# MC21R01_EtherCAT.net
KiCad netlist of a schematic drawn in Altium Designer
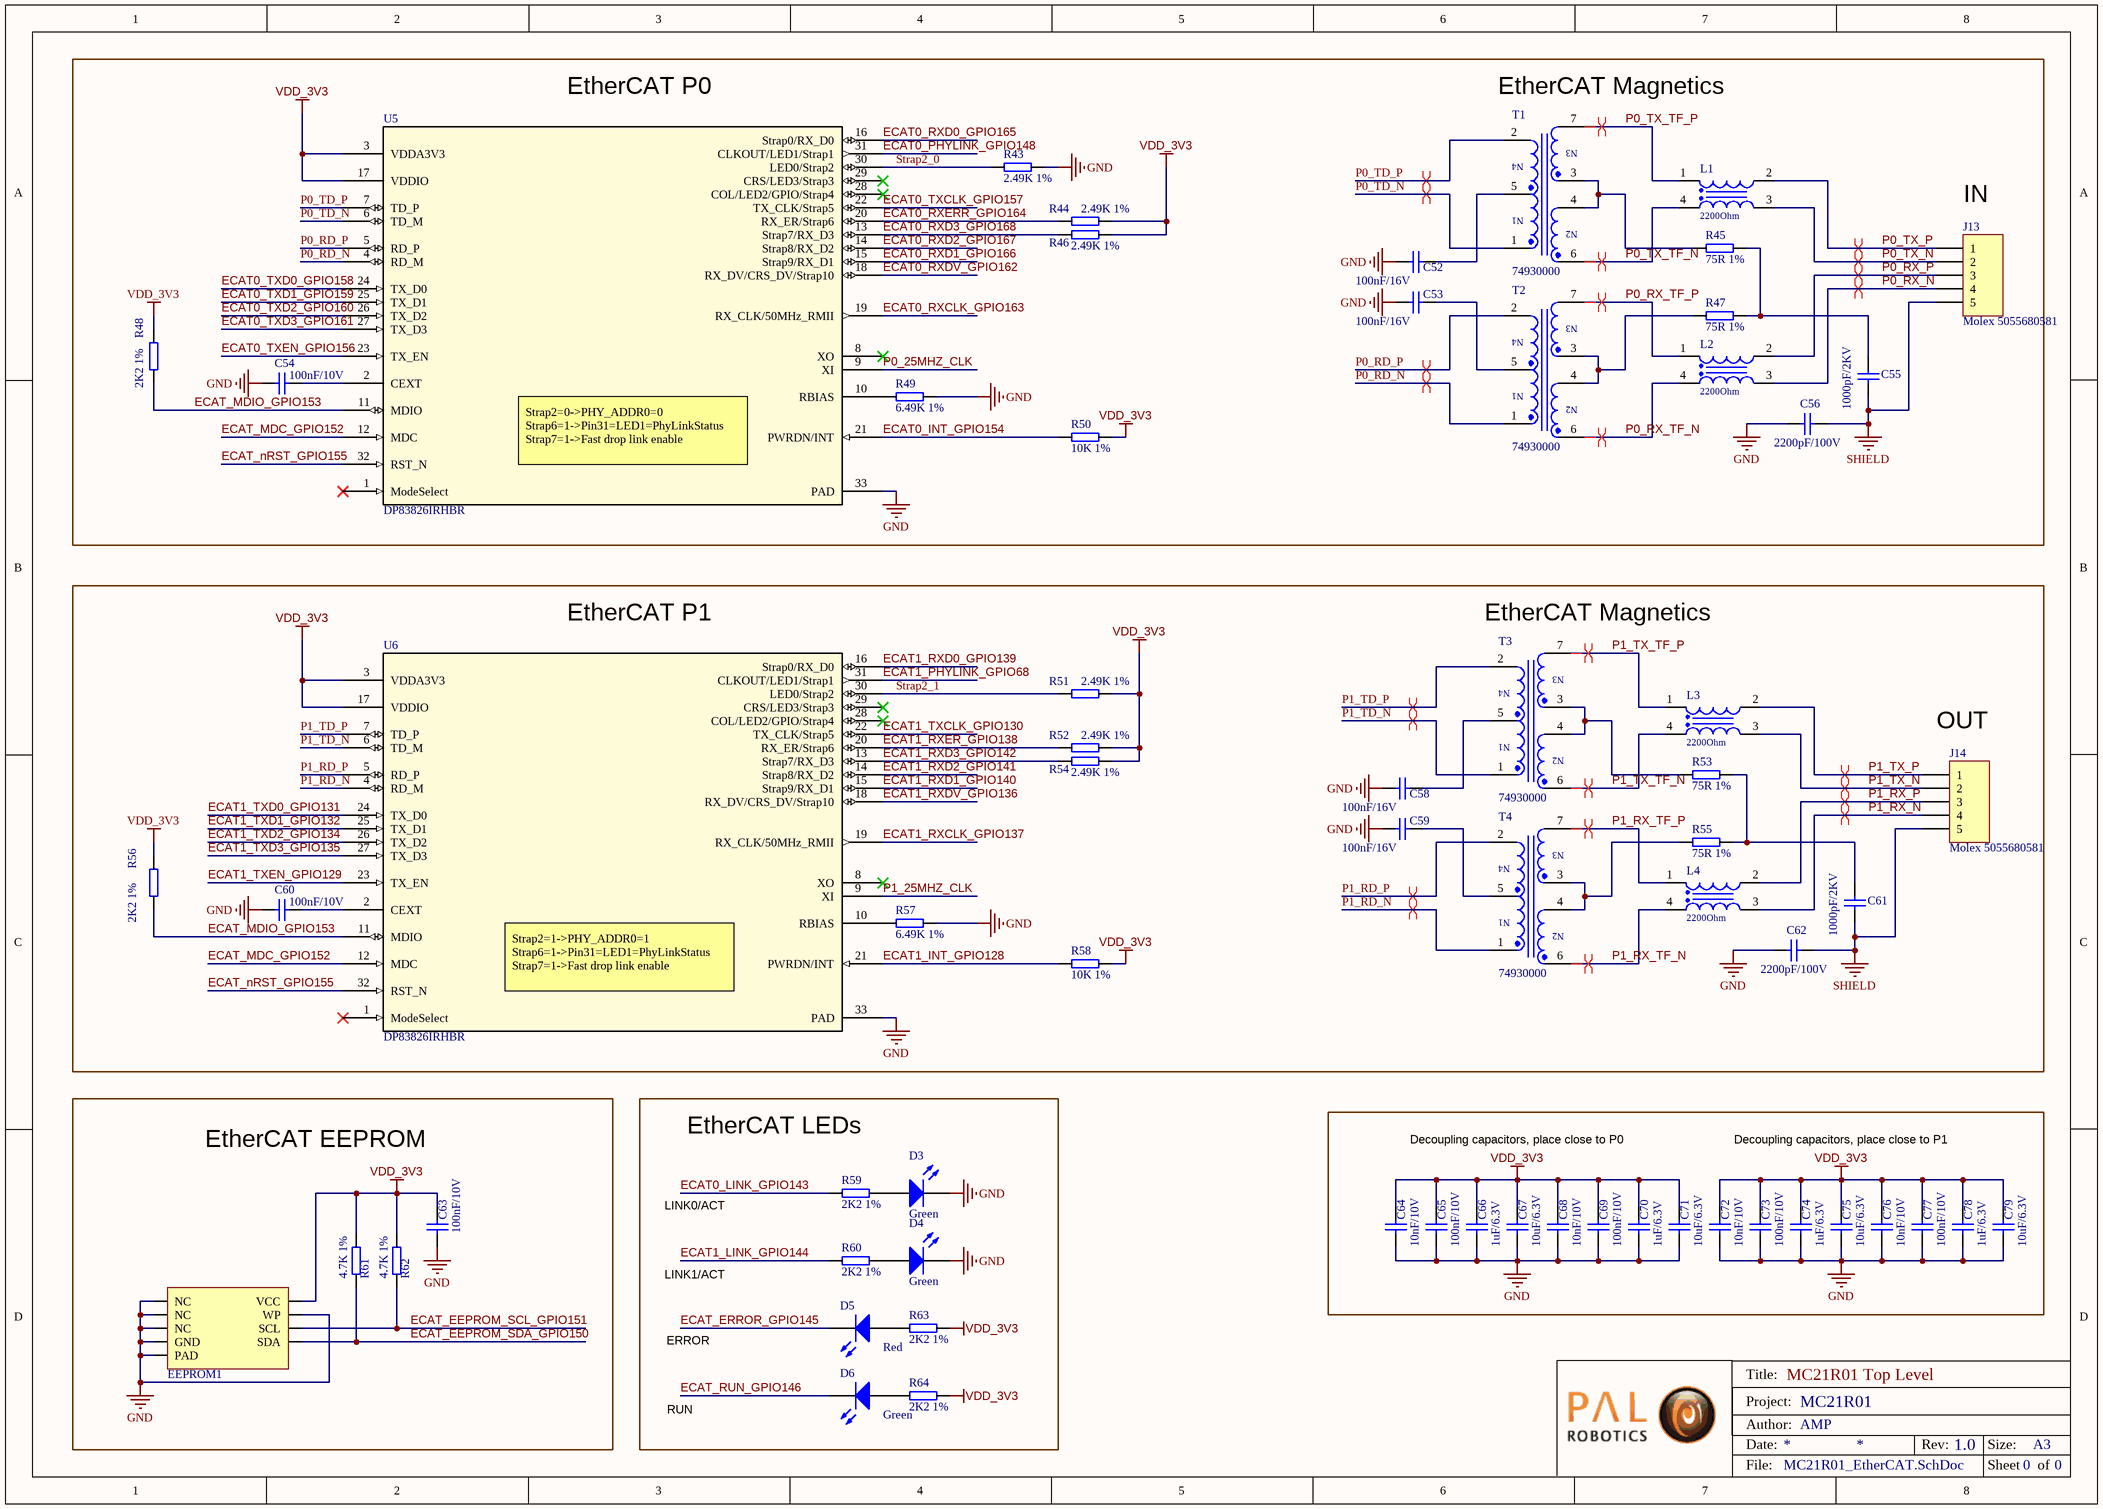
[diagram p0: MC21R01_EtherCAT.SchDoc]

(export (version "E")
  (design (tool "Eeschema 10.0.6"))
  (components
    (comp (ref "C52")
      (value "100nF/16V")
      (footprint "PAL_Capacitors:0402 SMD Capacitor")
      (description "100nF/16V 0402 10% Tolerance X7R Multilayer Ceramic Chip Capacitor")
      (fields (field (name "Comment") "100nF/16V 0402 10% X7R"))
      (libsource (lib "PAL_Capacitors") (part "100nF/16V 0402 10% X7R"))
    )
    (comp (ref "C53")
      (value "100nF/16V")
      (footprint "PAL_Capacitors:0402 SMD Capacitor")
      (description "100nF/16V 0402 10% Tolerance X7R Multilayer Ceramic Chip Capacitor")
      (fields (field (name "Comment") "100nF/16V 0402 10% X7R"))
      (libsource (lib "PAL_Capacitors") (part "100nF/16V 0402 10% X7R"))
    )
    (comp (ref "C54")
      (value "100nF/10V")
      (footprint "PAL_Capacitors:0402 SMD Capacitor")
      (description "100nF/10V 0402 20% Tolerance X5R Multilayer Ceramic Chip Capacitor")
      (fields (field (name "Comment") "100nF/10V 0402 20% X5R"))
      (libsource (lib "PAL_Capacitors") (part "100nF/10V 0402 20% X5R"))
    )
    (comp (ref "C55")
      (value "1000pF/2KV")
      (footprint "PAL_Capacitors:1206 SMD Capacitor")
      (description "1000 pF 2 KV 1206  ±10% Tolerance X7R Multilayer Ceramic Chip Capacitor")
      (libsource (lib "PAL_Capacitors") (part "1000pF/2KV 1206 10% X7R"))
    )
    (comp (ref "C56")
      (value "2200pF/100V")
      (footprint "PAL_Capacitors:0402 SMD Capacitor")
      (description "2200pF/100V 0402 10% Tolerance X7S Multilayer Ceramic Chip Capacitor")
      (fields (field (name "Comment") "2200pF/100V 0402 10% X7S"))
      (libsource (lib "PAL_Capacitors") (part "2200pF/100V 0402 10% X7S"))
    )
    (comp (ref "C58")
      (value "100nF/16V")
      (footprint "PAL_Capacitors:0402 SMD Capacitor")
      (description "100nF/16V 0402 10% Tolerance X7R Multilayer Ceramic Chip Capacitor")
      (fields (field (name "Comment") "100nF/16V 0402 10% X7R"))
      (libsource (lib "PAL_Capacitors") (part "100nF/16V 0402 10% X7R"))
    )
    (comp (ref "C59")
      (value "100nF/16V")
      (footprint "PAL_Capacitors:0402 SMD Capacitor")
      (description "100nF/16V 0402 10% Tolerance X7R Multilayer Ceramic Chip Capacitor")
      (fields (field (name "Comment") "100nF/16V 0402 10% X7R"))
      (libsource (lib "PAL_Capacitors") (part "100nF/16V 0402 10% X7R"))
    )
    (comp (ref "C60")
      (value "100nF/10V")
      (footprint "PAL_Capacitors:0402 SMD Capacitor")
      (description "100nF/10V 0402 20% Tolerance X5R Multilayer Ceramic Chip Capacitor")
      (fields (field (name "Comment") "100nF/10V 0402 20% X5R"))
      (libsource (lib "PAL_Capacitors") (part "100nF/10V 0402 20% X5R"))
    )
    (comp (ref "C61")
      (value "1000pF/2KV")
      (footprint "PAL_Capacitors:1206 SMD Capacitor")
      (description "1000 pF 2 KV 1206  ±10% Tolerance X7R Multilayer Ceramic Chip Capacitor")
      (libsource (lib "PAL_Capacitors") (part "1000pF/2KV 1206 10% X7R"))
    )
    (comp (ref "C62")
      (value "2200pF/100V")
      (footprint "PAL_Capacitors:0402 SMD Capacitor")
      (description "2200pF/100V 0402 10% Tolerance X7S Multilayer Ceramic Chip Capacitor")
      (fields (field (name "Comment") "2200pF/100V 0402 10% X7S"))
      (libsource (lib "PAL_Capacitors") (part "2200pF/100V 0402 10% X7S"))
    )
    (comp (ref "C63")
      (value "100nF/10V")
      (footprint "PAL_Capacitors:0402 SMD Capacitor")
      (description "100nF/10V 0402 20% Tolerance X5R Multilayer Ceramic Chip Capacitor")
      (fields (field (name "Comment") "100nF/10V 0402 20% X5R"))
      (libsource (lib "PAL_Capacitors") (part "100nF/10V 0402 20% X5R"))
    )
    (comp (ref "C64")
      (value "10nF/10V")
      (footprint "PAL_Capacitors:0402 SMD Capacitor")
      (description "10nF/10V 0402 20% Tolerance X5R Multilayer Ceramic Chip Capacitor")
      (fields (field (name "Comment") "10nF/10V 0402 20% X5R"))
      (libsource (lib "PAL_Capacitors") (part "10nF/10V 0402 20% X5R"))
    )
    (comp (ref "C65")
      (value "100nF/10V")
      (footprint "PAL_Capacitors:0402 SMD Capacitor")
      (description "100nF/10V 0402 20% Tolerance X5R Multilayer Ceramic Chip Capacitor")
      (fields (field (name "Comment") "100nF/10V 0402 20% X5R"))
      (libsource (lib "PAL_Capacitors") (part "100nF/10V 0402 20% X5R"))
    )
    (comp (ref "C66")
      (value "1uF/6.3V")
      (footprint "PAL_Capacitors:0402 SMD Capacitor")
      (description "1uF/6.3V 0402 10% Tolerance X5R Multilayer Ceramic Chip Capacitor")
      (fields (field (name "Comment") "1uF/6.3V 0402 10% X5R"))
      (libsource (lib "PAL_Capacitors") (part "1uF/6.3V 0402 10% X5R"))
    )
    (comp (ref "C67")
      (value "10uF/6.3V")
      (footprint "PAL_Capacitors:0402 SMD Capacitor")
      (description "10uF/6.3V 0402 20% Tolerance X5R Multilayer Ceramic Chip Capacitor")
      (fields (field (name "Comment") "10uF/6.3V 0402 20% X5R"))
      (libsource (lib "PAL_Capacitors") (part "10uF/6.3V 0402 20% X5R"))
    )
    (comp (ref "C68")
      (value "10nF/10V")
      (footprint "PAL_Capacitors:0402 SMD Capacitor")
      (description "10nF/10V 0402 20% Tolerance X5R Multilayer Ceramic Chip Capacitor")
      (fields (field (name "Comment") "10nF/10V 0402 20% X5R"))
      (libsource (lib "PAL_Capacitors") (part "10nF/10V 0402 20% X5R"))
    )
    (comp (ref "C69")
      (value "100nF/10V")
      (footprint "PAL_Capacitors:0402 SMD Capacitor")
      (description "100nF/10V 0402 20% Tolerance X5R Multilayer Ceramic Chip Capacitor")
      (fields (field (name "Comment") "100nF/10V 0402 20% X5R"))
      (libsource (lib "PAL_Capacitors") (part "100nF/10V 0402 20% X5R"))
    )
    (comp (ref "C70")
      (value "1uF/6.3V")
      (footprint "PAL_Capacitors:0402 SMD Capacitor")
      (description "1uF/6.3V 0402 10% Tolerance X5R Multilayer Ceramic Chip Capacitor")
      (fields (field (name "Comment") "1uF/6.3V 0402 10% X5R"))
      (libsource (lib "PAL_Capacitors") (part "1uF/6.3V 0402 10% X5R"))
    )
    (comp (ref "C71")
      (value "10uF/6.3V")
      (footprint "PAL_Capacitors:0402 SMD Capacitor")
      (description "10uF/6.3V 0402 20% Tolerance X5R Multilayer Ceramic Chip Capacitor")
      (fields (field (name "Comment") "10uF/6.3V 0402 20% X5R"))
      (libsource (lib "PAL_Capacitors") (part "10uF/6.3V 0402 20% X5R"))
    )
    (comp (ref "C72")
      (value "10nF/10V")
      (footprint "PAL_Capacitors:0402 SMD Capacitor")
      (description "10nF/10V 0402 20% Tolerance X5R Multilayer Ceramic Chip Capacitor")
      (fields (field (name "Comment") "10nF/10V 0402 20% X5R"))
      (libsource (lib "PAL_Capacitors") (part "10nF/10V 0402 20% X5R"))
    )
    (comp (ref "C73")
      (value "100nF/10V")
      (footprint "PAL_Capacitors:0402 SMD Capacitor")
      (description "100nF/10V 0402 20% Tolerance X5R Multilayer Ceramic Chip Capacitor")
      (fields (field (name "Comment") "100nF/10V 0402 20% X5R"))
      (libsource (lib "PAL_Capacitors") (part "100nF/10V 0402 20% X5R"))
    )
    (comp (ref "C74")
      (value "1uF/6.3V")
      (footprint "PAL_Capacitors:0402 SMD Capacitor")
      (description "1uF/6.3V 0402 10% Tolerance X5R Multilayer Ceramic Chip Capacitor")
      (fields (field (name "Comment") "1uF/6.3V 0402 10% X5R"))
      (libsource (lib "PAL_Capacitors") (part "1uF/6.3V 0402 10% X5R"))
    )
    (comp (ref "C75")
      (value "10uF/6.3V")
      (footprint "PAL_Capacitors:0402 SMD Capacitor")
      (description "10uF/6.3V 0402 20% Tolerance X5R Multilayer Ceramic Chip Capacitor")
      (fields (field (name "Comment") "10uF/6.3V 0402 20% X5R"))
      (libsource (lib "PAL_Capacitors") (part "10uF/6.3V 0402 20% X5R"))
    )
    (comp (ref "C76")
      (value "10nF/10V")
      (footprint "PAL_Capacitors:0402 SMD Capacitor")
      (description "10nF/10V 0402 20% Tolerance X5R Multilayer Ceramic Chip Capacitor")
      (fields (field (name "Comment") "10nF/10V 0402 20% X5R"))
      (libsource (lib "PAL_Capacitors") (part "10nF/10V 0402 20% X5R"))
    )
    (comp (ref "C77")
      (value "100nF/10V")
      (footprint "PAL_Capacitors:0402 SMD Capacitor")
      (description "100nF/10V 0402 20% Tolerance X5R Multilayer Ceramic Chip Capacitor")
      (fields (field (name "Comment") "100nF/10V 0402 20% X5R"))
      (libsource (lib "PAL_Capacitors") (part "100nF/10V 0402 20% X5R"))
    )
    (comp (ref "C78")
      (value "1uF/6.3V")
      (footprint "PAL_Capacitors:0402 SMD Capacitor")
      (description "1uF/6.3V 0402 10% Tolerance X5R Multilayer Ceramic Chip Capacitor")
      (fields (field (name "Comment") "1uF/6.3V 0402 10% X5R"))
      (libsource (lib "PAL_Capacitors") (part "1uF/6.3V 0402 10% X5R"))
    )
    (comp (ref "C79")
      (value "10uF/6.3V")
      (footprint "PAL_Capacitors:0402 SMD Capacitor")
      (description "10uF/6.3V 0402 20% Tolerance X5R Multilayer Ceramic Chip Capacitor")
      (fields (field (name "Comment") "10uF/6.3V 0402 20% X5R"))
      (libsource (lib "PAL_Capacitors") (part "10uF/6.3V 0402 20% X5R"))
    )
    (comp (ref "D3")
      (value "Green")
      (footprint "0402 SMD LED GREEN")
      (description "Low Profile Chip LED, Green")
      (fields (field (name "MANUFACTURER") "ROHM") (field (name "MANUFACTURER PART NUMBER") "SML-P11MTT86R"))
      (libsource (lib "PAL_devices") (part "LED_0402_green"))
    )
    (comp (ref "D4")
      (value "Green")
      (footprint "0402 SMD LED GREEN")
      (description "Low Profile Chip LED, Green")
      (fields (field (name "MANUFACTURER") "ROHM") (field (name "MANUFACTURER PART NUMBER") "SML-P11MTT86R"))
      (libsource (lib "PAL_devices") (part "LED_0402_green"))
    )
    (comp (ref "D5")
      (value "Red")
      (footprint "0402 SMD LED Red")
      (description "Low Profile Chip LED, Red")
      (fields (field (name "MANUFACTURER") "ROHM") (field (name "MANUFACTURER PART NUMBER") "SML-P11UTT86R"))
      (libsource (lib "PAL_devices") (part "LED_0402_Red"))
    )
    (comp (ref "D6")
      (value "Green")
      (footprint "0402 SMD LED GREEN")
      (description "Low Profile Chip LED, Green")
      (fields (field (name "MANUFACTURER") "ROHM") (field (name "MANUFACTURER PART NUMBER") "SML-P11MTT86R"))
      (libsource (lib "PAL_devices") (part "LED_0402_green"))
    )
    (comp (ref "EEPROM1")
      (value "CAT24C16HU4I-GT3")
      (footprint "PAL_IPC-7351_2020 :PQFN50P300X200X50_HS-9N")
      (description "CAT24C16 Series 16 Kb (2K x 8) 400 kHz I2C CMOS Serial EEPROM - UDFN-8EP")
      (fields (field (name "MANUFACTURER") "ON Semi") (field (name "CREATED BY") "AMP"))
      (libsource (lib "PAL_Memory_2020") (part "CAT24C16HU4I-GT3"))
    )
    (comp (ref "J13")
      (value "Molex 5055680581")
      (footprint "PAL_Molex_Micro-Lock_2020:Molex 5055680581")
      (fields
        (field (name "MANUFACTURER") "Molex")
        (field (name "MANUFACTURER PART NUMBER") "5055680581")
        (field (name "MATING PART NUMBER") "Molex 5055650501")
        (field (name "CREATED BY") "AMP")
      )
      (libsource (lib "PAL_Molex_Micro-Lock_2020") (part "Molex 5055680581"))
    )
    (comp (ref "J14")
      (value "Molex 5055680581")
      (footprint "PAL_Molex_Micro-Lock_2020:Molex 5055680581")
      (fields
        (field (name "MANUFACTURER") "Molex")
        (field (name "MANUFACTURER PART NUMBER") "5055680581")
        (field (name "MATING PART NUMBER") "Molex 5055650501")
        (field (name "CREATED BY") "AMP")
      )
      (libsource (lib "PAL_Molex_Micro-Lock_2020") (part "Molex 5055680581"))
    )
    (comp (ref "L1")
      (value "2200Ohm")
      (footprint "PAL_Wurth:744232222")
      (description "WE-CNSW SMT Common Mode Line Filter, size 1206, 2200Ohm, 0.2A, 50V")
      (fields
        (field (name "MANUFACTURER PART NUMBER") "744232222")
        (field (name "MANUFACTURER") "Wurth Elektronik")
      )
      (libsource (lib "PAL_Wurth") (part "744232222"))
    )
    (comp (ref "L2")
      (value "2200Ohm")
      (footprint "PAL_Wurth:744232222")
      (description "WE-CNSW SMT Common Mode Line Filter, size 1206, 2200Ohm, 0.2A, 50V")
      (fields
        (field (name "MANUFACTURER PART NUMBER") "744232222")
        (field (name "MANUFACTURER") "Wurth Elektronik")
      )
      (libsource (lib "PAL_Wurth") (part "744232222"))
    )
    (comp (ref "L3")
      (value "2200Ohm")
      (footprint "PAL_Wurth:744232222")
      (description "WE-CNSW SMT Common Mode Line Filter, size 1206, 2200Ohm, 0.2A, 50V")
      (fields
        (field (name "MANUFACTURER PART NUMBER") "744232222")
        (field (name "MANUFACTURER") "Wurth Elektronik")
      )
      (libsource (lib "PAL_Wurth") (part "744232222"))
    )
    (comp (ref "L4")
      (value "2200Ohm")
      (footprint "PAL_Wurth:744232222")
      (description "WE-CNSW SMT Common Mode Line Filter, size 1206, 2200Ohm, 0.2A, 50V")
      (fields
        (field (name "MANUFACTURER PART NUMBER") "744232222")
        (field (name "MANUFACTURER") "Wurth Elektronik")
      )
      (libsource (lib "PAL_Wurth") (part "744232222"))
    )
    (comp (ref "R43")
      (value "2.49K 1%")
      (footprint "0402 SMD rESISTOR")
      (description "2.49K/50V 1% 0402 100mW SMD Resistor")
      (libsource (lib "PAL_Resistors") (part "2.49K/50V 1% 0402 100mW"))
    )
    (comp (ref "R44")
      (value "2.49K 1%")
      (footprint "0402 SMD rESISTOR")
      (description "2.49K/50V 1% 0402 100mW SMD Resistor")
      (libsource (lib "PAL_Resistors") (part "2.49K/50V 1% 0402 100mW"))
    )
    (comp (ref "R45")
      (value "75R 1%")
      (footprint "0402 SMD rESISTOR")
      (description "75R/50V 1% 0402 100mW SMD Resistor")
      (libsource (lib "PAL_Resistors") (part "75R/50V 1% 0402 100mW"))
    )
    (comp (ref "R46")
      (value "2.49K 1%")
      (footprint "0402 SMD rESISTOR")
      (description "2.49K/50V 1% 0402 100mW SMD Resistor")
      (libsource (lib "PAL_Resistors") (part "2.49K/50V 1% 0402 100mW"))
    )
    (comp (ref "R47")
      (value "75R 1%")
      (footprint "0402 SMD rESISTOR")
      (description "75R/50V 1% 0402 100mW SMD Resistor")
      (libsource (lib "PAL_Resistors") (part "75R/50V 1% 0402 100mW"))
    )
    (comp (ref "R48")
      (value "2K2 1%")
      (footprint "0402 SMD rESISTOR")
      (description "2K2/50V 1% 0402 100mW SMD Resistor")
      (libsource (lib "PAL_Resistors") (part "2K2/50V 1% 0402 100mW"))
    )
    (comp (ref "R49")
      (value "6.49K 1%")
      (footprint "0402 SMD rESISTOR")
      (description "6.49K/50V 1% 0402 100mW SMD Resistor")
      (libsource (lib "PAL_Resistors") (part "6.49K/50V 1% 0402 100mW"))
    )
    (comp (ref "R50")
      (value "10K 1%")
      (footprint "0402 SMD rESISTOR")
      (description "10K/50V 1% 0402 100mW SMD Resistor")
      (libsource (lib "PAL_Resistors") (part "10K/50V 1% 0402 100mW"))
    )
    (comp (ref "R51")
      (value "2.49K 1%")
      (footprint "0402 SMD rESISTOR")
      (description "2.49K/50V 1% 0402 100mW SMD Resistor")
      (libsource (lib "PAL_Resistors") (part "2.49K/50V 1% 0402 100mW"))
    )
    (comp (ref "R52")
      (value "2.49K 1%")
      (footprint "0402 SMD rESISTOR")
      (description "2.49K/50V 1% 0402 100mW SMD Resistor")
      (libsource (lib "PAL_Resistors") (part "2.49K/50V 1% 0402 100mW"))
    )
    (comp (ref "R53")
      (value "75R 1%")
      (footprint "0402 SMD rESISTOR")
      (description "75R/50V 1% 0402 100mW SMD Resistor")
      (libsource (lib "PAL_Resistors") (part "75R/50V 1% 0402 100mW"))
    )
    (comp (ref "R54")
      (value "2.49K 1%")
      (footprint "0402 SMD rESISTOR")
      (description "2.49K/50V 1% 0402 100mW SMD Resistor")
      (libsource (lib "PAL_Resistors") (part "2.49K/50V 1% 0402 100mW"))
    )
    (comp (ref "R55")
      (value "75R 1%")
      (footprint "0402 SMD rESISTOR")
      (description "75R/50V 1% 0402 100mW SMD Resistor")
      (libsource (lib "PAL_Resistors") (part "75R/50V 1% 0402 100mW"))
    )
    (comp (ref "R56")
      (value "2K2 1%")
      (footprint "0402 SMD rESISTOR")
      (description "2K2/50V 1% 0402 100mW SMD Resistor")
      (libsource (lib "PAL_Resistors") (part "2K2/50V 1% 0402 100mW"))
    )
    (comp (ref "R57")
      (value "6.49K 1%")
      (footprint "0402 SMD rESISTOR")
      (description "6.49K/50V 1% 0402 100mW SMD Resistor")
      (libsource (lib "PAL_Resistors") (part "6.49K/50V 1% 0402 100mW"))
    )
    (comp (ref "R58")
      (value "10K 1%")
      (footprint "0402 SMD rESISTOR")
      (description "10K/50V 1% 0402 100mW SMD Resistor")
      (libsource (lib "PAL_Resistors") (part "10K/50V 1% 0402 100mW"))
    )
    (comp (ref "R59")
      (value "2K2 1%")
      (footprint "0402 SMD rESISTOR")
      (description "2K2/50V 1% 0402 100mW SMD Resistor")
      (libsource (lib "PAL_Resistors") (part "2K2/50V 1% 0402 100mW"))
    )
    (comp (ref "R60")
      (value "2K2 1%")
      (footprint "0402 SMD rESISTOR")
      (description "2K2/50V 1% 0402 100mW SMD Resistor")
      (libsource (lib "PAL_Resistors") (part "2K2/50V 1% 0402 100mW"))
    )
    (comp (ref "R61")
      (value "4.7K 1%")
      (footprint "0402 SMD rESISTOR")
      (description "4.7K/50V 1% 0402 100mW SMD Resistor")
      (libsource (lib "PAL_Resistors") (part "4.7K/50V 1% 0402 100mW"))
    )
    (comp (ref "R62")
      (value "4.7K 1%")
      (footprint "0402 SMD rESISTOR")
      (description "4.7K/50V 1% 0402 100mW SMD Resistor")
      (libsource (lib "PAL_Resistors") (part "4.7K/50V 1% 0402 100mW"))
    )
    (comp (ref "R63")
      (value "2K2 1%")
      (footprint "0402 SMD rESISTOR")
      (description "2K2/50V 1% 0402 100mW SMD Resistor")
      (libsource (lib "PAL_Resistors") (part "2K2/50V 1% 0402 100mW"))
    )
    (comp (ref "R64")
      (value "2K2 1%")
      (footprint "0402 SMD rESISTOR")
      (description "2K2/50V 1% 0402 100mW SMD Resistor")
      (libsource (lib "PAL_Resistors") (part "2K2/50V 1% 0402 100mW"))
    )
    (comp (ref "T1")
      (value "74930000")
      (footprint "PAL_Wurth:74930000")
      (description "WE-STST Super Tiny Signal Transformer, size 4532, 350uH")
      (fields (field (name "PUBLISHER") "Wurth Elektronik"))
      (libsource (lib "PAL_Wurth") (part "74930000"))
    )
    (comp (ref "T2")
      (value "74930000")
      (footprint "PAL_Wurth:74930000")
      (description "WE-STST Super Tiny Signal Transformer, size 4532, 350uH")
      (fields (field (name "PUBLISHER") "Wurth Elektronik"))
      (libsource (lib "PAL_Wurth") (part "74930000"))
    )
    (comp (ref "T3")
      (value "74930000")
      (footprint "PAL_Wurth:74930000")
      (description "WE-STST Super Tiny Signal Transformer, size 4532, 350uH")
      (fields (field (name "PUBLISHER") "Wurth Elektronik"))
      (libsource (lib "PAL_Wurth") (part "74930000"))
    )
    (comp (ref "T4")
      (value "74930000")
      (footprint "PAL_Wurth:74930000")
      (description "WE-STST Super Tiny Signal Transformer, size 4532, 350uH")
      (fields (field (name "PUBLISHER") "Wurth Elektronik"))
      (libsource (lib "PAL_Wurth") (part "74930000"))
    )
    (comp (ref "U5")
      (value "DP83826IRHBR")
      (footprint "RHB0032B")
      (fields (field (name "MANUFACTURER") "Texas Instruments"))
      (libsource (lib "TI-DP8382x") (part "DP83826IRHBR"))
    )
    (comp (ref "U6")
      (value "DP83826IRHBR")
      (footprint "RHB0032B")
      (fields (field (name "MANUFACTURER") "Texas Instruments"))
      (libsource (lib "TI-DP8382x") (part "DP83826IRHBR"))
    )
  )
  (nets
    (net (code "1") (name "/ECAT0_INT_GPIO154") (class "Default")
      (node (ref "R50") (pin "2") (pinfunction "2_2") (pintype "passive"))
      (node (ref "U5") (pin "21") (pinfunction "PWRDN/INT_21") (pintype "input"))
    )
    (net (code "2") (name "/ECAT0_LINK_GPIO143") (class "Default")
      (node (ref "R59") (pin "2") (pinfunction "2_2") (pintype "passive"))
    )
    (net (code "3") (name "/ECAT0_PHYLINK_GPIO148") (class "Default")
      (node (ref "U5") (pin "31") (pinfunction "CLKOUT/LED1/Strap1_31") (pintype "output"))
    )
    (net (code "4") (name "/ECAT0_RXCLK_GPIO163") (class "Default")
      (node (ref "U5") (pin "19") (pinfunction "RX_CLK/50MHz_RMII_19") (pintype "output"))
    )
    (net (code "5") (name "/ECAT0_RXD0_GPIO165") (class "Default")
      (node (ref "U5") (pin "16") (pinfunction "Strap0/RX_D0_16") (pintype "bidirectional"))
    )
    (net (code "6") (name "/ECAT0_RXD1_GPIO166") (class "Default")
      (node (ref "U5") (pin "15") (pinfunction "Strap9/RX_D1_15") (pintype "bidirectional"))
    )
    (net (code "7") (name "/ECAT0_RXD2_GPIO167") (class "Default")
      (node (ref "U5") (pin "14") (pinfunction "Strap8/RX_D2_14") (pintype "bidirectional"))
    )
    (net (code "8") (name "/ECAT0_RXD3_GPIO168") (class "Default")
      (node (ref "R46") (pin "1") (pinfunction "1_1") (pintype "passive"))
      (node (ref "U5") (pin "13") (pinfunction "Strap7/RX_D3_13") (pintype "bidirectional"))
    )
    (net (code "9") (name "/ECAT0_RXDV_GPIO162") (class "Default")
      (node (ref "U5") (pin "18") (pinfunction "RX_DV/CRS_DV/Strap10_18") (pintype "bidirectional"))
    )
    (net (code "10") (name "/ECAT0_RXERR_GPIO164") (class "Default")
      (node (ref "R44") (pin "2") (pinfunction "2_2") (pintype "passive"))
      (node (ref "U5") (pin "20") (pinfunction "RX_ER/Strap6_20") (pintype "bidirectional"))
    )
    (net (code "11") (name "/ECAT0_TXCLK_GPIO157") (class "Default")
      (node (ref "U5") (pin "22") (pinfunction "TX_CLK/Strap5_22") (pintype "bidirectional"))
    )
    (net (code "12") (name "/ECAT0_TXD0_GPIO158") (class "Default")
      (node (ref "U5") (pin "24") (pinfunction "TX_D0_24") (pintype "input"))
    )
    (net (code "13") (name "/ECAT0_TXD1_GPIO159") (class "Default")
      (node (ref "U5") (pin "25") (pinfunction "TX_D1_25") (pintype "input"))
    )
    (net (code "14") (name "/ECAT0_TXD2_GPIO160") (class "Default")
      (node (ref "U5") (pin "26") (pinfunction "TX_D2_26") (pintype "input"))
    )
    (net (code "15") (name "/ECAT0_TXD3_GPIO161") (class "Default")
      (node (ref "U5") (pin "27") (pinfunction "TX_D3_27") (pintype "input"))
    )
    (net (code "16") (name "/ECAT0_TXEN_GPIO156") (class "Default")
      (node (ref "U5") (pin "23") (pinfunction "TX_EN_23") (pintype "input"))
    )
    (net (code "17") (name "/ECAT1_INT_GPIO128") (class "Default")
      (node (ref "R58") (pin "2") (pinfunction "2_2") (pintype "passive"))
      (node (ref "U6") (pin "21") (pinfunction "PWRDN/INT_21") (pintype "input"))
    )
    (net (code "18") (name "/ECAT1_LINK_GPIO144") (class "Default")
      (node (ref "R60") (pin "2") (pinfunction "2_2") (pintype "passive"))
    )
    (net (code "19") (name "/ECAT1_PHYLINK_GPIO68") (class "Default")
      (node (ref "U6") (pin "31") (pinfunction "CLKOUT/LED1/Strap1_31") (pintype "output"))
    )
    (net (code "20") (name "/ECAT1_RXCLK_GPIO137") (class "Default")
      (node (ref "U6") (pin "19") (pinfunction "RX_CLK/50MHz_RMII_19") (pintype "output"))
    )
    (net (code "21") (name "/ECAT1_RXD0_GPIO139") (class "Default")
      (node (ref "U6") (pin "16") (pinfunction "Strap0/RX_D0_16") (pintype "bidirectional"))
    )
    (net (code "22") (name "/ECAT1_RXD1_GPIO140") (class "Default")
      (node (ref "U6") (pin "15") (pinfunction "Strap9/RX_D1_15") (pintype "bidirectional"))
    )
    (net (code "23") (name "/ECAT1_RXD2_GPIO141") (class "Default")
      (node (ref "U6") (pin "14") (pinfunction "Strap8/RX_D2_14") (pintype "bidirectional"))
    )
    (net (code "24") (name "/ECAT1_RXD3_GPIO142") (class "Default")
      (node (ref "R54") (pin "1") (pinfunction "1_1") (pintype "passive"))
      (node (ref "U6") (pin "13") (pinfunction "Strap7/RX_D3_13") (pintype "bidirectional"))
    )
    (net (code "25") (name "/ECAT1_RXDV_GPIO136") (class "Default")
      (node (ref "U6") (pin "18") (pinfunction "RX_DV/CRS_DV/Strap10_18") (pintype "bidirectional"))
    )
    (net (code "26") (name "/ECAT1_RXER_GPIO138") (class "Default")
      (node (ref "R52") (pin "2") (pinfunction "2_2") (pintype "passive"))
      (node (ref "U6") (pin "20") (pinfunction "RX_ER/Strap6_20") (pintype "bidirectional"))
    )
    (net (code "27") (name "/ECAT1_TXCLK_GPIO130") (class "Default")
      (node (ref "U6") (pin "22") (pinfunction "TX_CLK/Strap5_22") (pintype "bidirectional"))
    )
    (net (code "28") (name "/ECAT1_TXD0_GPIO131") (class "Default")
      (node (ref "U6") (pin "24") (pinfunction "TX_D0_24") (pintype "input"))
    )
    (net (code "29") (name "/ECAT1_TXD1_GPIO132") (class "Default")
      (node (ref "U6") (pin "25") (pinfunction "TX_D1_25") (pintype "input"))
    )
    (net (code "30") (name "/ECAT1_TXD2_GPIO134") (class "Default")
      (node (ref "U6") (pin "26") (pinfunction "TX_D2_26") (pintype "input"))
    )
    (net (code "31") (name "/ECAT1_TXD3_GPIO135") (class "Default")
      (node (ref "U6") (pin "27") (pinfunction "TX_D3_27") (pintype "input"))
    )
    (net (code "32") (name "/ECAT1_TXEN_GPIO129") (class "Default")
      (node (ref "U6") (pin "23") (pinfunction "TX_EN_23") (pintype "input"))
    )
    (net (code "33") (name "/ECAT_EEPROM_SCL_GPIO151") (class "Default")
      (node (ref "EEPROM1") (pin "6") (pinfunction "SCL_6") (pintype "passive"))
      (node (ref "R62") (pin "1") (pinfunction "1_1") (pintype "passive"))
    )
    (net (code "34") (name "/ECAT_EEPROM_SDA_GPIO150") (class "Default")
      (node (ref "EEPROM1") (pin "5") (pinfunction "SDA_5") (pintype "passive"))
      (node (ref "R61") (pin "1") (pinfunction "1_1") (pintype "passive"))
    )
    (net (code "35") (name "/ECAT_ERROR_GPIO145") (class "Default")
      (node (ref "D5") (pin "K") (pinfunction "K_K") (pintype "passive"))
    )
    (net (code "36") (name "/ECAT_MDC_GPIO152") (class "Default")
      (node (ref "U5") (pin "12") (pinfunction "MDC_12") (pintype "input"))
      (node (ref "U6") (pin "12") (pinfunction "MDC_12") (pintype "input"))
    )
    (net (code "37") (name "/ECAT_MDIO_GPIO153") (class "Default")
      (node (ref "R48") (pin "1") (pinfunction "1_1") (pintype "passive"))
      (node (ref "R56") (pin "1") (pinfunction "1_1") (pintype "passive"))
      (node (ref "U5") (pin "11") (pinfunction "MDIO_11") (pintype "bidirectional"))
      (node (ref "U6") (pin "11") (pinfunction "MDIO_11") (pintype "bidirectional"))
    )
    (net (code "38") (name "/ECAT_RUN_GPIO146") (class "Default")
      (node (ref "D6") (pin "K") (pinfunction "K_K") (pintype "passive"))
    )
    (net (code "39") (name "/ECAT_nRST_GPIO155") (class "Default")
      (node (ref "U5") (pin "32") (pinfunction "RST_N_32") (pintype "input"))
      (node (ref "U6") (pin "32") (pinfunction "RST_N_32") (pintype "input"))
    )
    (net (code "40") (name "/P0_25MHZ_CLK") (class "Default")
      (node (ref "U5") (pin "9") (pinfunction "XI_9") (pintype "passive"))
    )
    (net (code "41") (name "/P0_RD_N") (class "Default")
      (node (ref "T2") (pin "1") (pinfunction "1_1") (pintype "passive"))
      (node (ref "U5") (pin "4") (pinfunction "RD_M_4") (pintype "bidirectional"))
    )
    (net (code "42") (name "/P0_RD_P") (class "Default")
      (node (ref "T2") (pin "2") (pinfunction "2_2") (pintype "passive"))
      (node (ref "U5") (pin "5") (pinfunction "RD_P_5") (pintype "bidirectional"))
    )
    (net (code "43") (name "/P0_RX_N") (class "Default")
      (node (ref "J13") (pin "4") (pinfunction "4_4") (pintype "passive"))
      (node (ref "L2") (pin "3") (pinfunction "3_3") (pintype "passive"))
    )
    (net (code "44") (name "/P0_RX_P") (class "Default")
      (node (ref "J13") (pin "3") (pinfunction "3_3") (pintype "passive"))
      (node (ref "L2") (pin "2") (pinfunction "2_2") (pintype "passive"))
    )
    (net (code "45") (name "/P0_RX_TF_N") (class "Default")
      (node (ref "L2") (pin "4") (pinfunction "4_4") (pintype "passive"))
      (node (ref "T2") (pin "6") (pinfunction "6_6") (pintype "passive"))
    )
    (net (code "46") (name "/P0_RX_TF_P") (class "Default")
      (node (ref "L2") (pin "1") (pinfunction "1_1") (pintype "passive"))
      (node (ref "T2") (pin "7") (pinfunction "7_7") (pintype "passive"))
    )
    (net (code "47") (name "/P0_TD_N") (class "Default")
      (node (ref "T1") (pin "1") (pinfunction "1_1") (pintype "passive"))
      (node (ref "U5") (pin "6") (pinfunction "TD_M_6") (pintype "bidirectional"))
    )
    (net (code "48") (name "/P0_TD_P") (class "Default")
      (node (ref "T1") (pin "2") (pinfunction "2_2") (pintype "passive"))
      (node (ref "U5") (pin "7") (pinfunction "TD_P_7") (pintype "bidirectional"))
    )
    (net (code "49") (name "/P0_TX_N") (class "Default")
      (node (ref "J13") (pin "2") (pinfunction "2_2") (pintype "passive"))
      (node (ref "L1") (pin "3") (pinfunction "3_3") (pintype "passive"))
    )
    (net (code "50") (name "/P0_TX_P") (class "Default")
      (node (ref "J13") (pin "1") (pinfunction "1_1") (pintype "passive"))
      (node (ref "L1") (pin "2") (pinfunction "2_2") (pintype "passive"))
    )
    (net (code "51") (name "/P0_TX_TF_N") (class "Default")
      (node (ref "L1") (pin "4") (pinfunction "4_4") (pintype "passive"))
      (node (ref "T1") (pin "6") (pinfunction "6_6") (pintype "passive"))
    )
    (net (code "52") (name "/P0_TX_TF_P") (class "Default")
      (node (ref "L1") (pin "1") (pinfunction "1_1") (pintype "passive"))
      (node (ref "T1") (pin "7") (pinfunction "7_7") (pintype "passive"))
    )
    (net (code "53") (name "/P1_25MHZ_CLK") (class "Default")
      (node (ref "U6") (pin "9") (pinfunction "XI_9") (pintype "passive"))
    )
    (net (code "54") (name "/P1_RD_N") (class "Default")
      (node (ref "T4") (pin "1") (pinfunction "1_1") (pintype "passive"))
      (node (ref "U6") (pin "4") (pinfunction "RD_M_4") (pintype "bidirectional"))
    )
    (net (code "55") (name "/P1_RD_P") (class "Default")
      (node (ref "T4") (pin "2") (pinfunction "2_2") (pintype "passive"))
      (node (ref "U6") (pin "5") (pinfunction "RD_P_5") (pintype "bidirectional"))
    )
    (net (code "56") (name "/P1_RX_N") (class "Default")
      (node (ref "J14") (pin "4") (pinfunction "4_4") (pintype "passive"))
      (node (ref "L4") (pin "3") (pinfunction "3_3") (pintype "passive"))
    )
    (net (code "57") (name "/P1_RX_P") (class "Default")
      (node (ref "J14") (pin "3") (pinfunction "3_3") (pintype "passive"))
      (node (ref "L4") (pin "2") (pinfunction "2_2") (pintype "passive"))
    )
    (net (code "58") (name "/P1_RX_TF_N") (class "Default")
      (node (ref "L4") (pin "4") (pinfunction "4_4") (pintype "passive"))
      (node (ref "T4") (pin "6") (pinfunction "6_6") (pintype "passive"))
    )
    (net (code "59") (name "/P1_RX_TF_P") (class "Default")
      (node (ref "L4") (pin "1") (pinfunction "1_1") (pintype "passive"))
      (node (ref "T4") (pin "7") (pinfunction "7_7") (pintype "passive"))
    )
    (net (code "60") (name "/P1_TD_N") (class "Default")
      (node (ref "T3") (pin "1") (pinfunction "1_1") (pintype "passive"))
      (node (ref "U6") (pin "6") (pinfunction "TD_M_6") (pintype "bidirectional"))
    )
    (net (code "61") (name "/P1_TD_P") (class "Default")
      (node (ref "T3") (pin "2") (pinfunction "2_2") (pintype "passive"))
      (node (ref "U6") (pin "7") (pinfunction "TD_P_7") (pintype "bidirectional"))
    )
    (net (code "62") (name "/P1_TX_N") (class "Default")
      (node (ref "J14") (pin "2") (pinfunction "2_2") (pintype "passive"))
      (node (ref "L3") (pin "3") (pinfunction "3_3") (pintype "passive"))
    )
    (net (code "63") (name "/P1_TX_P") (class "Default")
      (node (ref "J14") (pin "1") (pinfunction "1_1") (pintype "passive"))
      (node (ref "L3") (pin "2") (pinfunction "2_2") (pintype "passive"))
    )
    (net (code "64") (name "/P1_TX_TF_N") (class "Default")
      (node (ref "L3") (pin "4") (pinfunction "4_4") (pintype "passive"))
      (node (ref "T3") (pin "6") (pinfunction "6_6") (pintype "passive"))
    )
    (net (code "65") (name "/P1_TX_TF_P") (class "Default")
      (node (ref "L3") (pin "1") (pinfunction "1_1") (pintype "passive"))
      (node (ref "T3") (pin "7") (pinfunction "7_7") (pintype "passive"))
    )
    (net (code "66") (name "/Strap2_0") (class "Default")
      (node (ref "R43") (pin "2") (pinfunction "2_2") (pintype "passive"))
      (node (ref "U5") (pin "30") (pinfunction "LED0/Strap2_30") (pintype "bidirectional"))
    )
    (net (code "67") (name "/Strap2_1") (class "Default")
      (node (ref "R51") (pin "2") (pinfunction "2_2") (pintype "passive"))
      (node (ref "U6") (pin "30") (pinfunction "LED0/Strap2_30") (pintype "bidirectional"))
    )
    (net (code "68") (name "GND") (class "Default")
      (node (ref "C52") (pin "1") (pinfunction "1_1") (pintype "passive"))
      (node (ref "C53") (pin "1") (pinfunction "1_1") (pintype "passive"))
      (node (ref "C54") (pin "2") (pinfunction "2_2") (pintype "passive"))
      (node (ref "C56") (pin "1") (pinfunction "1_1") (pintype "passive"))
      (node (ref "C58") (pin "1") (pinfunction "1_1") (pintype "passive"))
      (node (ref "C59") (pin "1") (pinfunction "1_1") (pintype "passive"))
      (node (ref "C60") (pin "2") (pinfunction "2_2") (pintype "passive"))
      (node (ref "C62") (pin "1") (pinfunction "1_1") (pintype "passive"))
      (node (ref "C63") (pin "2") (pinfunction "2_2") (pintype "passive"))
      (node (ref "C64") (pin "2") (pinfunction "2_2") (pintype "passive"))
      (node (ref "C65") (pin "2") (pinfunction "2_2") (pintype "passive"))
      (node (ref "C66") (pin "2") (pinfunction "2_2") (pintype "passive"))
      (node (ref "C67") (pin "2") (pinfunction "2_2") (pintype "passive"))
      (node (ref "C68") (pin "2") (pinfunction "2_2") (pintype "passive"))
      (node (ref "C69") (pin "2") (pinfunction "2_2") (pintype "passive"))
      (node (ref "C70") (pin "2") (pinfunction "2_2") (pintype "passive"))
      (node (ref "C71") (pin "2") (pinfunction "2_2") (pintype "passive"))
      (node (ref "C72") (pin "2") (pinfunction "2_2") (pintype "passive"))
      (node (ref "C73") (pin "2") (pinfunction "2_2") (pintype "passive"))
      (node (ref "C74") (pin "2") (pinfunction "2_2") (pintype "passive"))
      (node (ref "C75") (pin "2") (pinfunction "2_2") (pintype "passive"))
      (node (ref "C76") (pin "2") (pinfunction "2_2") (pintype "passive"))
      (node (ref "C77") (pin "2") (pinfunction "2_2") (pintype "passive"))
      (node (ref "C78") (pin "2") (pinfunction "2_2") (pintype "passive"))
      (node (ref "C79") (pin "2") (pinfunction "2_2") (pintype "passive"))
      (node (ref "D3") (pin "K") (pinfunction "K_K") (pintype "passive"))
      (node (ref "D4") (pin "K") (pinfunction "K_K") (pintype "passive"))
      (node (ref "EEPROM1") (pin "1") (pinfunction "NC_1") (pintype "passive"))
      (node (ref "EEPROM1") (pin "2") (pinfunction "NC_2") (pintype "passive"))
      (node (ref "EEPROM1") (pin "3") (pinfunction "NC_3") (pintype "passive"))
      (node (ref "EEPROM1") (pin "4") (pinfunction "GND_4") (pintype "passive"))
      (node (ref "EEPROM1") (pin "7") (pinfunction "WP_7") (pintype "passive"))
      (node (ref "EEPROM1") (pin "9") (pinfunction "PAD_9") (pintype "passive"))
      (node (ref "R43") (pin "1") (pinfunction "1_1") (pintype "passive"))
      (node (ref "R49") (pin "2") (pinfunction "2_2") (pintype "passive"))
      (node (ref "R57") (pin "2") (pinfunction "2_2") (pintype "passive"))
      (node (ref "U5") (pin "33") (pinfunction "PAD_33") (pintype "power_in"))
      (node (ref "U6") (pin "33") (pinfunction "PAD_33") (pintype "power_in"))
    )
    (net (code "69") (name "Net-(C52-Pad2)") (class "Default")
      (node (ref "C52") (pin "2") (pinfunction "2_2") (pintype "passive"))
      (node (ref "T1") (pin "5") (pinfunction "5_5") (pintype "passive"))
    )
    (net (code "70") (name "Net-(C53-Pad2)") (class "Default")
      (node (ref "C53") (pin "2") (pinfunction "2_2") (pintype "passive"))
      (node (ref "T2") (pin "5") (pinfunction "5_5") (pintype "passive"))
    )
    (net (code "71") (name "Net-(C55-Pad1)") (class "Default")
      (node (ref "C55") (pin "1") (pinfunction "1_1") (pintype "passive"))
      (node (ref "R45") (pin "1") (pinfunction "1_1") (pintype "passive"))
      (node (ref "R47") (pin "1") (pinfunction "1_1") (pintype "passive"))
    )
    (net (code "72") (name "Net-(C58-Pad2)") (class "Default")
      (node (ref "C58") (pin "2") (pinfunction "2_2") (pintype "passive"))
      (node (ref "T3") (pin "5") (pinfunction "5_5") (pintype "passive"))
    )
    (net (code "73") (name "Net-(C59-Pad2)") (class "Default")
      (node (ref "C59") (pin "2") (pinfunction "2_2") (pintype "passive"))
      (node (ref "T4") (pin "5") (pinfunction "5_5") (pintype "passive"))
    )
    (net (code "74") (name "Net-(C61-Pad1)") (class "Default")
      (node (ref "C61") (pin "1") (pinfunction "1_1") (pintype "passive"))
      (node (ref "R53") (pin "1") (pinfunction "1_1") (pintype "passive"))
      (node (ref "R55") (pin "1") (pinfunction "1_1") (pintype "passive"))
    )
    (net (code "75") (name "Net-(D3-PadA)") (class "Default")
      (node (ref "D3") (pin "A") (pinfunction "A_A") (pintype "passive"))
      (node (ref "R59") (pin "1") (pinfunction "1_1") (pintype "passive"))
    )
    (net (code "76") (name "Net-(D4-PadA)") (class "Default")
      (node (ref "D4") (pin "A") (pinfunction "A_A") (pintype "passive"))
      (node (ref "R60") (pin "1") (pinfunction "1_1") (pintype "passive"))
    )
    (net (code "77") (name "Net-(D5-PadA)") (class "Default")
      (node (ref "D5") (pin "A") (pinfunction "A_A") (pintype "passive"))
      (node (ref "R63") (pin "2") (pinfunction "2_2") (pintype "passive"))
    )
    (net (code "78") (name "Net-(D6-PadA)") (class "Default")
      (node (ref "D6") (pin "A") (pinfunction "A_A") (pintype "passive"))
      (node (ref "R64") (pin "2") (pinfunction "2_2") (pintype "passive"))
    )
    (net (code "79") (name "Net-(R45-Pad2)") (class "Default")
      (node (ref "R45") (pin "2") (pinfunction "2_2") (pintype "passive"))
      (node (ref "T1") (pin "3") (pinfunction "3_3") (pintype "passive"))
      (node (ref "T1") (pin "4") (pinfunction "4_4") (pintype "passive"))
    )
    (net (code "80") (name "Net-(R47-Pad2)") (class "Default")
      (node (ref "R47") (pin "2") (pinfunction "2_2") (pintype "passive"))
      (node (ref "T2") (pin "3") (pinfunction "3_3") (pintype "passive"))
      (node (ref "T2") (pin "4") (pinfunction "4_4") (pintype "passive"))
    )
    (net (code "81") (name "Net-(R53-Pad2)") (class "Default")
      (node (ref "R53") (pin "2") (pinfunction "2_2") (pintype "passive"))
      (node (ref "T3") (pin "3") (pinfunction "3_3") (pintype "passive"))
      (node (ref "T3") (pin "4") (pinfunction "4_4") (pintype "passive"))
    )
    (net (code "82") (name "Net-(R55-Pad2)") (class "Default")
      (node (ref "R55") (pin "2") (pinfunction "2_2") (pintype "passive"))
      (node (ref "T4") (pin "3") (pinfunction "3_3") (pintype "passive"))
      (node (ref "T4") (pin "4") (pinfunction "4_4") (pintype "passive"))
    )
    (net (code "83") (name "Net-(U5-CEXT)") (class "Default")
      (node (ref "C54") (pin "1") (pinfunction "1_1") (pintype "passive"))
      (node (ref "U5") (pin "2") (pinfunction "CEXT_2") (pintype "passive"))
    )
    (net (code "84") (name "Net-(U5-RBIAS)") (class "Default")
      (node (ref "R49") (pin "1") (pinfunction "1_1") (pintype "passive"))
      (node (ref "U5") (pin "10") (pinfunction "RBIAS_10") (pintype "passive"))
    )
    (net (code "85") (name "Net-(U6-CEXT)") (class "Default")
      (node (ref "C60") (pin "1") (pinfunction "1_1") (pintype "passive"))
      (node (ref "U6") (pin "2") (pinfunction "CEXT_2") (pintype "passive"))
    )
    (net (code "86") (name "Net-(U6-RBIAS)") (class "Default")
      (node (ref "R57") (pin "1") (pinfunction "1_1") (pintype "passive"))
      (node (ref "U6") (pin "10") (pinfunction "RBIAS_10") (pintype "passive"))
    )
    (net (code "87") (name "SHIELD") (class "Default")
      (node (ref "C55") (pin "2") (pinfunction "2_2") (pintype "passive"))
      (node (ref "C56") (pin "2") (pinfunction "2_2") (pintype "passive"))
      (node (ref "C61") (pin "2") (pinfunction "2_2") (pintype "passive"))
      (node (ref "C62") (pin "2") (pinfunction "2_2") (pintype "passive"))
      (node (ref "J13") (pin "5") (pinfunction "5_5") (pintype "passive"))
      (node (ref "J14") (pin "5") (pinfunction "5_5") (pintype "passive"))
    )
    (net (code "88") (name "VDD_3V3") (class "Default")
      (node (ref "C63") (pin "1") (pinfunction "1_1") (pintype "passive"))
      (node (ref "C64") (pin "1") (pinfunction "1_1") (pintype "passive"))
      (node (ref "C65") (pin "1") (pinfunction "1_1") (pintype "passive"))
      (node (ref "C66") (pin "1") (pinfunction "1_1") (pintype "passive"))
      (node (ref "C67") (pin "1") (pinfunction "1_1") (pintype "passive"))
      (node (ref "C68") (pin "1") (pinfunction "1_1") (pintype "passive"))
      (node (ref "C69") (pin "1") (pinfunction "1_1") (pintype "passive"))
      (node (ref "C70") (pin "1") (pinfunction "1_1") (pintype "passive"))
      (node (ref "C71") (pin "1") (pinfunction "1_1") (pintype "passive"))
      (node (ref "C72") (pin "1") (pinfunction "1_1") (pintype "passive"))
      (node (ref "C73") (pin "1") (pinfunction "1_1") (pintype "passive"))
      (node (ref "C74") (pin "1") (pinfunction "1_1") (pintype "passive"))
      (node (ref "C75") (pin "1") (pinfunction "1_1") (pintype "passive"))
      (node (ref "C76") (pin "1") (pinfunction "1_1") (pintype "passive"))
      (node (ref "C77") (pin "1") (pinfunction "1_1") (pintype "passive"))
      (node (ref "C78") (pin "1") (pinfunction "1_1") (pintype "passive"))
      (node (ref "C79") (pin "1") (pinfunction "1_1") (pintype "passive"))
      (node (ref "EEPROM1") (pin "8") (pinfunction "VCC_8") (pintype "passive"))
      (node (ref "R44") (pin "1") (pinfunction "1_1") (pintype "passive"))
      (node (ref "R46") (pin "2") (pinfunction "2_2") (pintype "passive"))
      (node (ref "R48") (pin "2") (pinfunction "2_2") (pintype "passive"))
      (node (ref "R50") (pin "1") (pinfunction "1_1") (pintype "passive"))
      (node (ref "R51") (pin "1") (pinfunction "1_1") (pintype "passive"))
      (node (ref "R52") (pin "1") (pinfunction "1_1") (pintype "passive"))
      (node (ref "R54") (pin "2") (pinfunction "2_2") (pintype "passive"))
      (node (ref "R56") (pin "2") (pinfunction "2_2") (pintype "passive"))
      (node (ref "R58") (pin "1") (pinfunction "1_1") (pintype "passive"))
      (node (ref "R61") (pin "2") (pinfunction "2_2") (pintype "passive"))
      (node (ref "R62") (pin "2") (pinfunction "2_2") (pintype "passive"))
      (node (ref "R63") (pin "1") (pinfunction "1_1") (pintype "passive"))
      (node (ref "R64") (pin "1") (pinfunction "1_1") (pintype "passive"))
      (node (ref "U5") (pin "17") (pinfunction "VDDIO_17") (pintype "power_in"))
      (node (ref "U5") (pin "3") (pinfunction "VDDA3V3_3") (pintype "power_in"))
      (node (ref "U6") (pin "17") (pinfunction "VDDIO_17") (pintype "power_in"))
      (node (ref "U6") (pin "3") (pinfunction "VDDA3V3_3") (pintype "power_in"))
    )
    (net (code "89") (name "unconnected-(U5-COL{slash}LED2{slash}GPIO{slash}Strap4-Pad28)") (class "Default")
      (node (ref "U5") (pin "28") (pinfunction "COL/LED2/GPIO/Strap4_28") (pintype "bidirectional+no_connect"))
    )
    (net (code "90") (name "unconnected-(U5-CRS{slash}LED3{slash}Strap3-Pad29)") (class "Default")
      (node (ref "U5") (pin "29") (pinfunction "CRS/LED3/Strap3_29") (pintype "bidirectional+no_connect"))
    )
    (net (code "91") (name "unconnected-(U5-ModeSelect-Pad1)") (class "Default")
      (node (ref "U5") (pin "1") (pinfunction "ModeSelect_1") (pintype "input+no_connect"))
    )
    (net (code "92") (name "unconnected-(U5-XO-Pad8)") (class "Default")
      (node (ref "U5") (pin "8") (pinfunction "XO_8") (pintype "passive+no_connect"))
    )
    (net (code "93") (name "unconnected-(U6-COL{slash}LED2{slash}GPIO{slash}Strap4-Pad28)") (class "Default")
      (node (ref "U6") (pin "28") (pinfunction "COL/LED2/GPIO/Strap4_28") (pintype "bidirectional+no_connect"))
    )
    (net (code "94") (name "unconnected-(U6-CRS{slash}LED3{slash}Strap3-Pad29)") (class "Default")
      (node (ref "U6") (pin "29") (pinfunction "CRS/LED3/Strap3_29") (pintype "bidirectional+no_connect"))
    )
    (net (code "95") (name "unconnected-(U6-ModeSelect-Pad1)") (class "Default")
      (node (ref "U6") (pin "1") (pinfunction "ModeSelect_1") (pintype "input+no_connect"))
    )
    (net (code "96") (name "unconnected-(U6-XO-Pad8)") (class "Default")
      (node (ref "U6") (pin "8") (pinfunction "XO_8") (pintype "passive+no_connect"))
    )
  )
)
